# MCU_STM32H743VIT6.net
KiCad netlist of a schematic drawn in Altium Designer
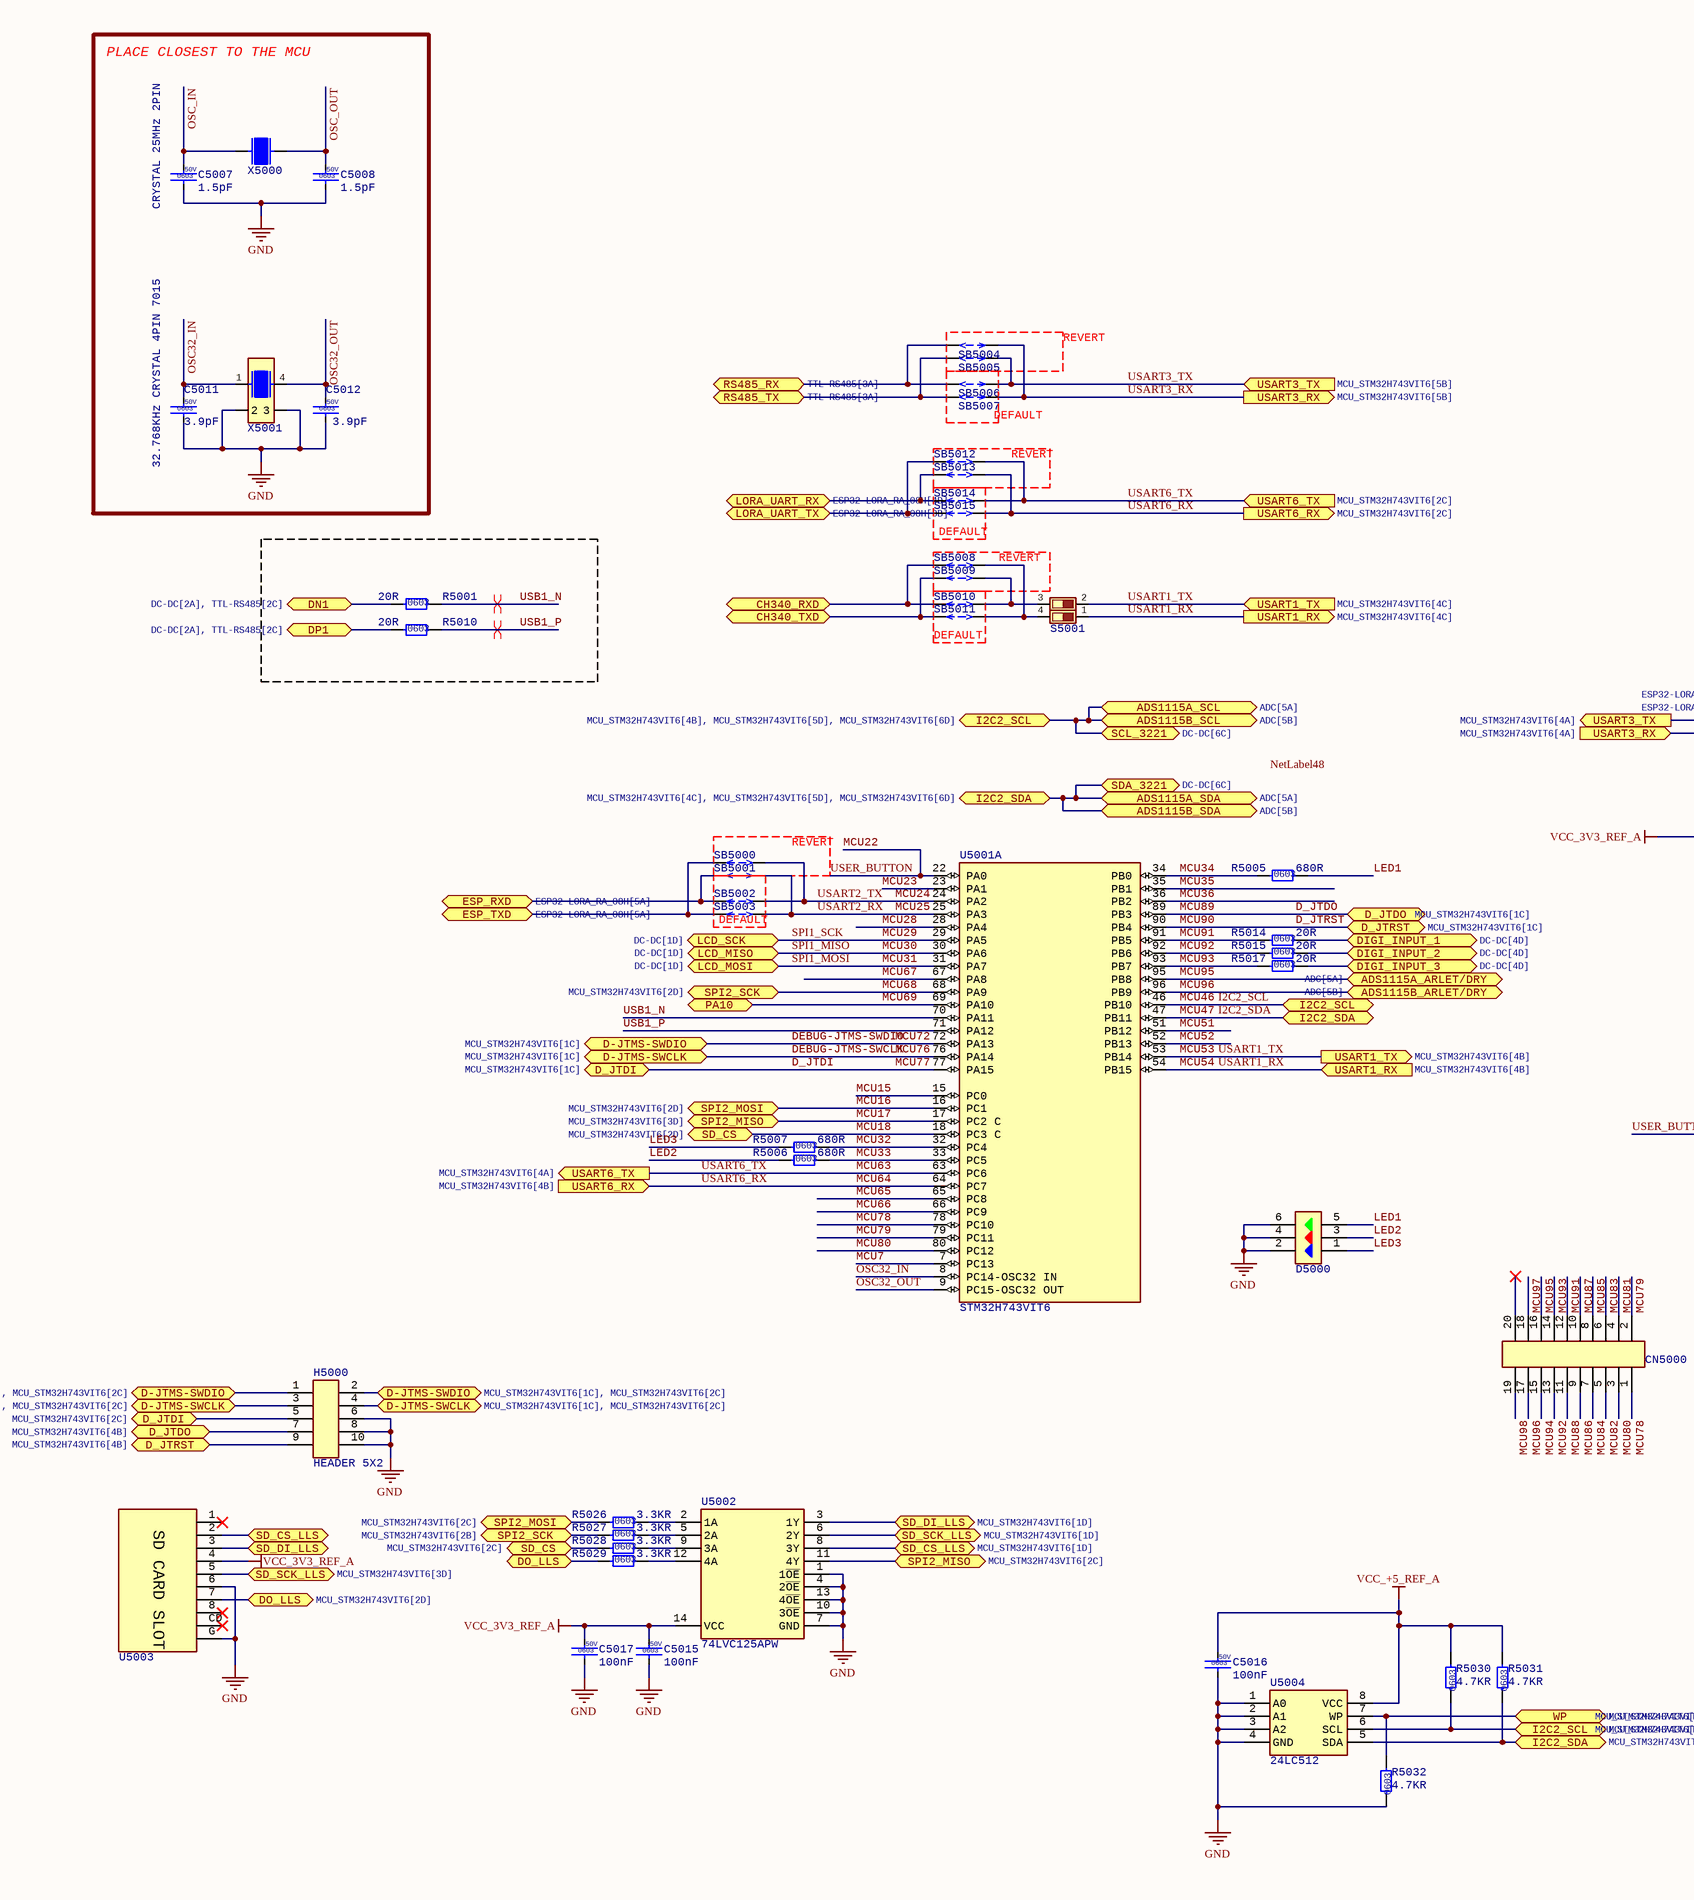
[diagram p0: MCU_STM32H743VIT6.SchDoc, left]
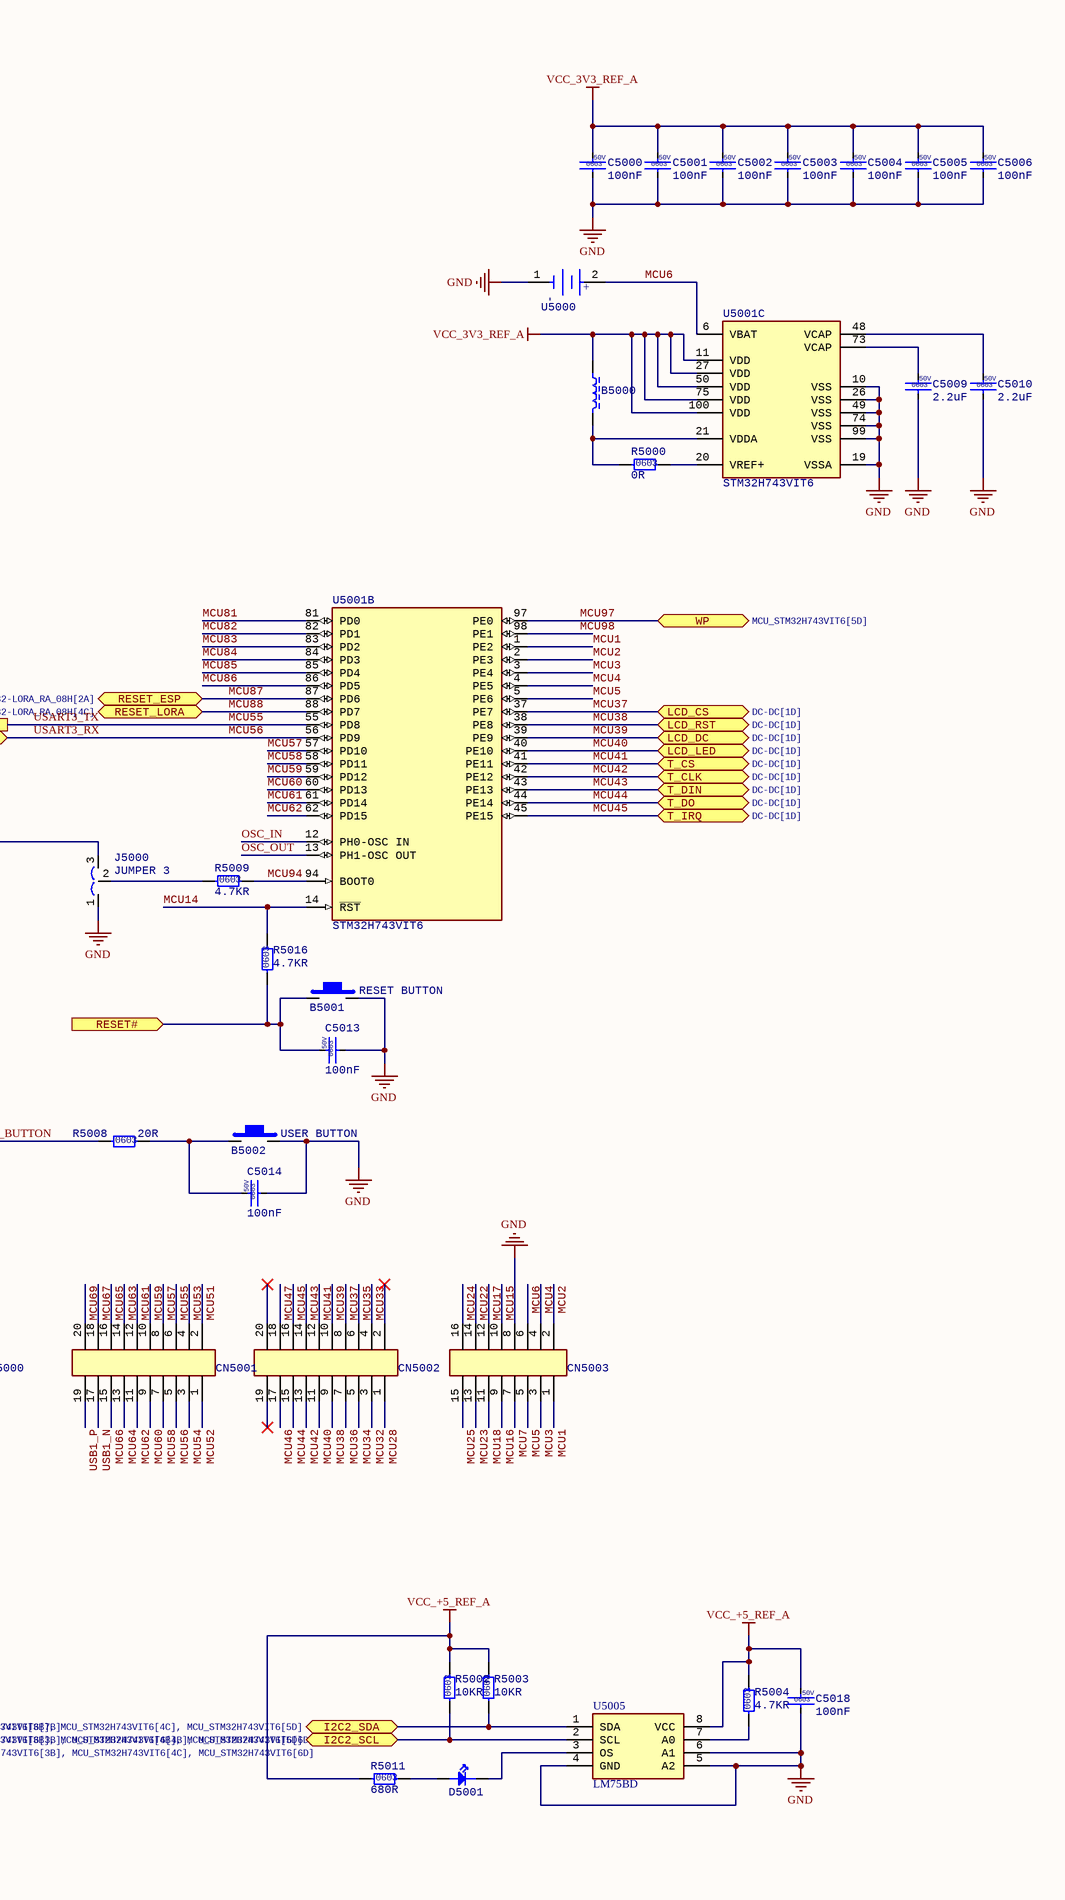
[diagram p1: MCU_STM32H743VIT6.SchDoc, right]

(export (version "E")
  (design (tool "Eeschema 10.0.6"))
  (components
    (comp (ref "B5000")
      (value "FERRITE BEAD 600 OHM")
      (footprint "FERRITE BEAD 0603")
      (description "FERRITE BEAD 600 OHM 0603 1LN")
      (libsource (lib "FF_FINAL_PROJECT") (part "FERRITE BEAD"))
    )
    (comp (ref "B5001")
      (value "RESET BUTTON")
      (footprint "TACTILE 3X4MM")
      (description "Nút Nhấn 3x4mm Cao 2.5mm 2 Chân SMD")
      (libsource (lib "FF_FINAL_PROJECT") (part "TACTILE 3X4MM"))
    )
    (comp (ref "B5002")
      (value "USER BUTTON")
      (footprint "TACTILE 3X4MM")
      (description "Nút Nhấn 3x4mm Cao 2.5mm 2 Chân SMD")
      (libsource (lib "FF_FINAL_PROJECT") (part "TACTILE 3X4MM"))
    )
    (comp (ref "C5000")
      (value "100nF")
      (footprint "CAP CER 0603")
      (description "CAP CER SMD 100nF 10% 50V 0603")
      (fields (field (name "VOLTAGE") "50V") (field (name "SIZE") "0603") (field (name "TOLERANCE") "10%"))
      (libsource (lib "FF_FINAL_PROJECT") (part "CAPACITOR CERAMIC"))
    )
    (comp (ref "C5001")
      (value "100nF")
      (footprint "CAP CER 0603")
      (description "CAP CER SMD 100nF 10% 50V 0603")
      (fields (field (name "VOLTAGE") "50V") (field (name "SIZE") "0603") (field (name "TOLERANCE") "10%"))
      (libsource (lib "FF_FINAL_PROJECT") (part "CAPACITOR CERAMIC"))
    )
    (comp (ref "C5002")
      (value "100nF")
      (footprint "CAP CER 0603")
      (description "CAP CER SMD 100nF 10% 50V 0603")
      (fields (field (name "VOLTAGE") "50V") (field (name "SIZE") "0603") (field (name "TOLERANCE") "10%"))
      (libsource (lib "FF_FINAL_PROJECT") (part "CAPACITOR CERAMIC"))
    )
    (comp (ref "C5003")
      (value "100nF")
      (footprint "CAP CER 0603")
      (description "CAP CER SMD 100nF 10% 50V 0603")
      (fields (field (name "VOLTAGE") "50V") (field (name "SIZE") "0603") (field (name "TOLERANCE") "10%"))
      (libsource (lib "FF_FINAL_PROJECT") (part "CAPACITOR CERAMIC"))
    )
    (comp (ref "C5004")
      (value "100nF")
      (footprint "CAP CER 0603")
      (description "CAP CER SMD 100nF 10% 50V 0603")
      (fields (field (name "VOLTAGE") "50V") (field (name "SIZE") "0603") (field (name "TOLERANCE") "10%"))
      (libsource (lib "FF_FINAL_PROJECT") (part "CAPACITOR CERAMIC"))
    )
    (comp (ref "C5005")
      (value "100nF")
      (footprint "CAP CER 0603")
      (description "CAP CER SMD 100nF 10% 50V 0603")
      (fields (field (name "VOLTAGE") "50V") (field (name "SIZE") "0603") (field (name "TOLERANCE") "10%"))
      (libsource (lib "FF_FINAL_PROJECT") (part "CAPACITOR CERAMIC"))
    )
    (comp (ref "C5006")
      (value "100nF")
      (footprint "CAP CER 0603")
      (description "CAP CER SMD 100nF 10% 50V 0603")
      (fields (field (name "VOLTAGE") "50V") (field (name "SIZE") "0603") (field (name "TOLERANCE") "10%"))
      (libsource (lib "FF_FINAL_PROJECT") (part "CAPACITOR CERAMIC"))
    )
    (comp (ref "C5007")
      (value "1.5pF")
      (footprint "CAP CER 0603")
      (description "CAP CER SMD 1.5pF 10% 50V 0603")
      (fields (field (name "VOLTAGE") "50V") (field (name "SIZE") "0603") (field (name "TOLERANCE") "10%"))
      (libsource (lib "FF_FINAL_PROJECT") (part "CAPACITOR CERAMIC"))
    )
    (comp (ref "C5008")
      (value "1.5pF")
      (footprint "CAP CER 0603")
      (description "CAP CER SMD 1.5pF 10% 50V 0603")
      (fields (field (name "VOLTAGE") "50V") (field (name "SIZE") "0603") (field (name "TOLERANCE") "10%"))
      (libsource (lib "FF_FINAL_PROJECT") (part "CAPACITOR CERAMIC"))
    )
    (comp (ref "C5009")
      (value "2.2uF")
      (footprint "CAP CER 0603")
      (description "CAP CER SMD 2.2uF 10% 50V 0603")
      (fields (field (name "VOLTAGE") "50V") (field (name "SIZE") "0603") (field (name "TOLERANCE") "10%"))
      (libsource (lib "FF_FINAL_PROJECT") (part "CAPACITOR CERAMIC"))
    )
    (comp (ref "C5010")
      (value "2.2uF")
      (footprint "CAP CER 0603")
      (description "CAP CER SMD 2.2uF 10% 50V 0603")
      (fields (field (name "VOLTAGE") "50V") (field (name "SIZE") "0603") (field (name "TOLERANCE") "10%"))
      (libsource (lib "FF_FINAL_PROJECT") (part "CAPACITOR CERAMIC"))
    )
    (comp (ref "C5011")
      (value "3.9pF")
      (footprint "CAP CER 0603")
      (description "CAP CER SMD 3.9pF 10% 50V 0603")
      (fields (field (name "VOLTAGE") "50V") (field (name "SIZE") "0603") (field (name "TOLERANCE") "10%"))
      (libsource (lib "FF_FINAL_PROJECT") (part "CAPACITOR CERAMIC"))
    )
    (comp (ref "C5012")
      (value "3.9pF")
      (footprint "CAP CER 0603")
      (description "CAP CER SMD 3.9pF 10% 50V 0603")
      (fields (field (name "VOLTAGE") "50V") (field (name "SIZE") "0603") (field (name "TOLERANCE") "10%"))
      (libsource (lib "FF_FINAL_PROJECT") (part "CAPACITOR CERAMIC"))
    )
    (comp (ref "C5013")
      (value "100nF")
      (footprint "CAP CER 0603")
      (description "CAP CER SMD 100nF 10% 50V 0603")
      (fields (field (name "VOLTAGE") "50V") (field (name "SIZE") "0603") (field (name "TOLERANCE") "10%"))
      (libsource (lib "FF_FINAL_PROJECT") (part "CAPACITOR CERAMIC"))
    )
    (comp (ref "C5014")
      (value "100nF")
      (footprint "CAP CER 0603")
      (description "CAP CER SMD 100nF 10% 50V 0603")
      (fields (field (name "VOLTAGE") "50V") (field (name "SIZE") "0603") (field (name "TOLERANCE") "10%"))
      (libsource (lib "FF_FINAL_PROJECT") (part "CAPACITOR CERAMIC"))
    )
    (comp (ref "C5015")
      (value "100nF")
      (footprint "CAP CER 0603")
      (description "CAP CER SMD 100nF 10% 50V 0603")
      (fields (field (name "VOLTAGE") "50V") (field (name "SIZE") "0603") (field (name "TOLERANCE") "10%"))
      (libsource (lib "FF_FINAL_PROJECT") (part "CAPACITOR CERAMIC"))
    )
    (comp (ref "C5016")
      (value "100nF")
      (footprint "CAP CER 0603")
      (description "CAP CER SMD 100nF 10% 50V 0603")
      (fields (field (name "VOLTAGE") "50V") (field (name "SIZE") "0603") (field (name "TOLERANCE") "10%"))
      (libsource (lib "FF_FINAL_PROJECT") (part "CAPACITOR CERAMIC"))
    )
    (comp (ref "C5017")
      (value "100nF")
      (footprint "CAP CER 0603")
      (description "CAP CER SMD 100nF 10% 50V 0603")
      (fields (field (name "VOLTAGE") "50V") (field (name "SIZE") "0603") (field (name "TOLERANCE") "10%"))
      (libsource (lib "FF_FINAL_PROJECT") (part "CAPACITOR CERAMIC"))
    )
    (comp (ref "C5018")
      (value "100nF")
      (footprint "CAP CER 0603")
      (description "CAP CER SMD 100nF 10% 50V 0603")
      (fields (field (name "VOLTAGE") "50V") (field (name "SIZE") "0603") (field (name "TOLERANCE") "10%"))
      (libsource (lib "FF_FINAL_PROJECT") (part "CAPACITOR CERAMIC"))
    )
    (comp (ref "CN5000")
      (value "SMD HEADER 10X2X2.54MM")
      (footprint "SMD HEADER 10X2X2.54MM")
      (libsource (lib "FF_FINAL_PROJECT") (part "SMD HEADER 10X2X2.54MM"))
    )
    (comp (ref "CN5001")
      (value "SMD HEADER 10X2X2.54MM")
      (footprint "SMD HEADER 10X2X2.54MM")
      (libsource (lib "FF_FINAL_PROJECT") (part "SMD HEADER 10X2X2.54MM"))
    )
    (comp (ref "CN5002")
      (value "SMD HEADER 10X2X2.54MM")
      (footprint "SMD HEADER 10X2X2.54MM")
      (libsource (lib "FF_FINAL_PROJECT") (part "SMD HEADER 10X2X2.54MM"))
    )
    (comp (ref "CN5003")
      (value "SMD HEADER 8X2X2.54MM")
      (footprint "SMD HEADER 8X2X2.54MM")
      (libsource (lib "FF_FINAL_PROJECT") (part "SMD HEADER 8X2X2.54MM"))
    )
    (comp (ref "D5000")
      (value "LED RGB 5050")
      (footprint "LED RGB 5050")
      (description "LED RGB 5050 Dán SMD Trong Suốt")
      (libsource (lib "FF_FINAL_PROJECT") (part "LED RGB"))
    )
    (comp (ref "D5001")
      (value "LED RED")
      (footprint "LED RED 0603")
      (description "LED RED 0603")
      (libsource (lib "FF_FINAL_PROJECT") (part "LED"))
    )
    (comp (ref "H5000")
      (value "HEADER 5X2")
      (footprint "HEADER 5X2")
      (libsource (lib "FF_FINAL_PROJECT") (part "HEADER 5X2"))
    )
    (comp (ref "J5000")
      (value "JUMPER 3")
      (footprint "JUMPER 3")
      (libsource (lib "FF_FINAL_PROJECT") (part "JUMPER 3"))
    )
    (comp (ref "R5000")
      (value "0R")
      (footprint "RESC 0603(1608) SMD")
      (description "RESISTOR SMD 0R OHM 1% 100mW 0603")
      (fields (field (name "SIZE") "0603") (field (name "TOLERANCE") "1%"))
      (libsource (lib "FF_FINAL_PROJECT") (part "RESISTOR"))
    )
    (comp (ref "R5001")
      (value "20R")
      (footprint "RESC 0603(1608) SMD")
      (description "RESISTOR SMD 20R OHM 1% 100mW 0603")
      (fields (field (name "SIZE") "0603") (field (name "TOLERANCE") "1%"))
      (libsource (lib "FF_FINAL_PROJECT") (part "RESISTOR"))
    )
    (comp (ref "R5002")
      (value "10KR")
      (footprint "RESC 0603(1608) SMD")
      (description "RESISTOR SMD 10KR OHM 1% 100mW 0603")
      (fields (field (name "SIZE") "0603") (field (name "TOLERANCE") "1%"))
      (libsource (lib "") (part "RESISTOR_2"))
    )
    (comp (ref "R5003")
      (value "10KR")
      (footprint "RESC 0603(1608) SMD")
      (description "RESISTOR SMD 10KR OHM 1% 100mW 0603")
      (fields (field (name "SIZE") "0603") (field (name "TOLERANCE") "1%"))
      (libsource (lib "") (part "RESISTOR_2"))
    )
    (comp (ref "R5004")
      (value "4.7KR")
      (footprint "RESC 0603(1608) SMD")
      (description "RESISTOR SMD 4.7KR OHM 1% 100mW 0603")
      (fields (field (name "SIZE") "0603") (field (name "TOLERANCE") "1%"))
      (libsource (lib "") (part "RESISTOR_2"))
    )
    (comp (ref "R5005")
      (value "680R")
      (footprint "RESC 0603(1608) SMD")
      (description "RESISTOR SMD 680R OHM 5% 100mW 0603")
      (fields (field (name "SIZE") "0603") (field (name "TOLERANCE") "5%"))
      (libsource (lib "FF_FINAL_PROJECT") (part "RESISTOR"))
    )
    (comp (ref "R5006")
      (value "680R")
      (footprint "RESC 0603(1608) SMD")
      (description "RESISTOR SMD 680R OHM 5% 100mW 0603")
      (fields (field (name "SIZE") "0603") (field (name "TOLERANCE") "5%"))
      (libsource (lib "FF_FINAL_PROJECT") (part "RESISTOR"))
    )
    (comp (ref "R5007")
      (value "680R")
      (footprint "RESC 0603(1608) SMD")
      (description "RESISTOR SMD 680R OHM 5% 100mW 0603")
      (fields (field (name "SIZE") "0603") (field (name "TOLERANCE") "5%"))
      (libsource (lib "FF_FINAL_PROJECT") (part "RESISTOR"))
    )
    (comp (ref "R5008")
      (value "20R")
      (footprint "RESC 0603(1608) SMD")
      (description "RESISTOR SMD 20R OHM 1% 100mW 0603")
      (fields (field (name "SIZE") "0603") (field (name "TOLERANCE") "1%"))
      (libsource (lib "FF_FINAL_PROJECT") (part "RESISTOR"))
    )
    (comp (ref "R5009")
      (value "4.7KR")
      (footprint "RESC 0603(1608) SMD")
      (description "RESISTOR SMD 4.7KR OHM 1% 100mW 0603")
      (fields (field (name "SIZE") "0603") (field (name "TOLERANCE") "1%"))
      (libsource (lib "FF_FINAL_PROJECT") (part "RESISTOR"))
    )
    (comp (ref "R5010")
      (value "20R")
      (footprint "RESC 0603(1608) SMD")
      (description "RESISTOR SMD 20R OHM 1% 100mW 0603")
      (fields (field (name "SIZE") "0603") (field (name "TOLERANCE") "1%"))
      (libsource (lib "FF_FINAL_PROJECT") (part "RESISTOR"))
    )
    (comp (ref "R5011")
      (value "680R")
      (footprint "RESC 0603(1608) SMD")
      (description "RESISTOR SMD 680R OHM 5% 100mW 0603")
      (fields (field (name "SIZE") "0603") (field (name "TOLERANCE") "5%"))
      (libsource (lib "FF_FINAL_PROJECT") (part "RESISTOR"))
    )
    (comp (ref "R5014")
      (value "20R")
      (footprint "RESC 0603(1608) SMD")
      (description "RESISTOR SMD 20R OHM 1% 100mW 0603")
      (fields (field (name "SIZE") "0603") (field (name "TOLERANCE") "1%"))
      (libsource (lib "FF_FINAL_PROJECT") (part "RESISTOR"))
    )
    (comp (ref "R5015")
      (value "20R")
      (footprint "RESC 0603(1608) SMD")
      (description "RESISTOR SMD 20R OHM 1% 100mW 0603")
      (fields (field (name "SIZE") "0603") (field (name "TOLERANCE") "1%"))
      (libsource (lib "FF_FINAL_PROJECT") (part "RESISTOR"))
    )
    (comp (ref "R5016")
      (value "4.7KR")
      (footprint "RESC 0603(1608) SMD")
      (description "RESISTOR SMD 4.7KR OHM 1% 100mW 0603")
      (fields (field (name "SIZE") "0603") (field (name "TOLERANCE") "1%"))
      (libsource (lib "") (part "RESISTOR_2"))
    )
    (comp (ref "R5017")
      (value "20R")
      (footprint "RESC 0603(1608) SMD")
      (description "RESISTOR SMD 20R OHM 1% 100mW 0603")
      (fields (field (name "SIZE") "0603") (field (name "TOLERANCE") "1%"))
      (libsource (lib "FF_FINAL_PROJECT") (part "RESISTOR"))
    )
    (comp (ref "R5026")
      (value "3.3KR")
      (footprint "RESC 0603(1608) SMD")
      (description "RESISTOR SMD 3.3KR OHM 1% 100mW 0603")
      (fields (field (name "SIZE") "0603") (field (name "TOLERANCE") "1%"))
      (libsource (lib "FF_FINAL_PROJECT") (part "RESISTOR"))
    )
    (comp (ref "R5027")
      (value "3.3KR")
      (footprint "RESC 0603(1608) SMD")
      (description "RESISTOR SMD 3.3KR OHM 1% 100mW 0603")
      (fields (field (name "SIZE") "0603") (field (name "TOLERANCE") "1%"))
      (libsource (lib "FF_FINAL_PROJECT") (part "RESISTOR"))
    )
    (comp (ref "R5028")
      (value "3.3KR")
      (footprint "RESC 0603(1608) SMD")
      (description "RESISTOR SMD 3.3KR OHM 1% 100mW 0603")
      (fields (field (name "SIZE") "0603") (field (name "TOLERANCE") "1%"))
      (libsource (lib "FF_FINAL_PROJECT") (part "RESISTOR"))
    )
    (comp (ref "R5029")
      (value "3.3KR")
      (footprint "RESC 0603(1608) SMD")
      (description "RESISTOR SMD 3.3KR OHM 1% 100mW 0603")
      (fields (field (name "SIZE") "0603") (field (name "TOLERANCE") "1%"))
      (libsource (lib "FF_FINAL_PROJECT") (part "RESISTOR"))
    )
    (comp (ref "R5030")
      (value "4.7KR")
      (footprint "RESC 0603(1608) SMD")
      (description "RESISTOR SMD 4.7KR OHM 1% 100mW 0603")
      (fields (field (name "SIZE") "0603") (field (name "TOLERANCE") "1%"))
      (libsource (lib "") (part "RESISTOR_1"))
    )
    (comp (ref "R5031")
      (value "4.7KR")
      (footprint "RESC 0603(1608) SMD")
      (description "RESISTOR SMD 4.7KR OHM 1% 100mW 0603")
      (fields (field (name "SIZE") "0603") (field (name "TOLERANCE") "1%"))
      (libsource (lib "") (part "RESISTOR_1"))
    )
    (comp (ref "R5032")
      (value "4.7KR")
      (footprint "RESC 0603(1608) SMD")
      (description "RESISTOR SMD 4.7KR OHM 1% 100mW 0603")
      (fields (field (name "SIZE") "0603") (field (name "TOLERANCE") "1%"))
      (libsource (lib "") (part "RESISTOR_1"))
    )
    (comp (ref "S5001")
      (value "DIP-2")
      (footprint "DIP-2 SWITCH")
      (description "DIP SWITCH 1.27mm 2 CONTACT")
      (libsource (lib "FF_FINAL_PROJECT") (part "DIP-2 SWITCH"))
    )
    (comp (ref "SB5000")
      (value "SB")
      (footprint "SB")
      (description "RESISTOR SMD 0R OHM 1% 100mW 0603")
      (fields (field (name "TOLERANCE") "1%"))
      (libsource (lib "FF_FINAL_PROJECT") (part "SB"))
    )
    (comp (ref "SB5001")
      (value "SB")
      (footprint "SB")
      (description "RESISTOR SMD 0R OHM 1% 100mW 0603")
      (fields (field (name "TOLERANCE") "1%"))
      (libsource (lib "FF_FINAL_PROJECT") (part "SB"))
    )
    (comp (ref "SB5002")
      (value "SB")
      (footprint "SB")
      (description "RESISTOR SMD 0R OHM 1% 100mW 0603")
      (fields (field (name "TOLERANCE") "1%"))
      (libsource (lib "FF_FINAL_PROJECT") (part "SB"))
    )
    (comp (ref "SB5003")
      (value "SB")
      (footprint "SB")
      (description "RESISTOR SMD 0R OHM 1% 100mW 0603")
      (fields (field (name "TOLERANCE") "1%"))
      (libsource (lib "FF_FINAL_PROJECT") (part "SB"))
    )
    (comp (ref "SB5004")
      (value "SB")
      (footprint "SB")
      (description "RESISTOR SMD 0R OHM 1% 100mW 0603")
      (fields (field (name "TOLERANCE") "1%"))
      (libsource (lib "FF_FINAL_PROJECT") (part "SB"))
    )
    (comp (ref "SB5005")
      (value "SB")
      (footprint "SB")
      (description "RESISTOR SMD 0R OHM 1% 100mW 0603")
      (fields (field (name "TOLERANCE") "1%"))
      (libsource (lib "FF_FINAL_PROJECT") (part "SB"))
    )
    (comp (ref "SB5006")
      (value "SB")
      (footprint "SB")
      (description "RESISTOR SMD 0R OHM 1% 100mW 0603")
      (fields (field (name "TOLERANCE") "1%"))
      (libsource (lib "FF_FINAL_PROJECT") (part "SB"))
    )
    (comp (ref "SB5007")
      (value "SB")
      (footprint "SB")
      (description "RESISTOR SMD 0R OHM 1% 100mW 0603")
      (fields (field (name "TOLERANCE") "1%"))
      (libsource (lib "FF_FINAL_PROJECT") (part "SB"))
    )
    (comp (ref "SB5008")
      (value "SB")
      (footprint "SB")
      (description "RESISTOR SMD 0R OHM 1% 100mW 0603")
      (fields (field (name "TOLERANCE") "1%"))
      (libsource (lib "FF_FINAL_PROJECT") (part "SB"))
    )
    (comp (ref "SB5009")
      (value "SB")
      (footprint "SB")
      (description "RESISTOR SMD 0R OHM 1% 100mW 0603")
      (fields (field (name "TOLERANCE") "1%"))
      (libsource (lib "FF_FINAL_PROJECT") (part "SB"))
    )
    (comp (ref "SB5010")
      (value "SB")
      (footprint "SB")
      (description "RESISTOR SMD 0R OHM 1% 100mW 0603")
      (fields (field (name "TOLERANCE") "1%"))
      (libsource (lib "FF_FINAL_PROJECT") (part "SB"))
    )
    (comp (ref "SB5011")
      (value "SB")
      (footprint "SB")
      (description "RESISTOR SMD 0R OHM 1% 100mW 0603")
      (fields (field (name "TOLERANCE") "1%"))
      (libsource (lib "FF_FINAL_PROJECT") (part "SB"))
    )
    (comp (ref "SB5012")
      (value "SB")
      (footprint "SB")
      (description "RESISTOR SMD 0R OHM 1% 100mW 0603")
      (fields (field (name "TOLERANCE") "1%"))
      (libsource (lib "FF_FINAL_PROJECT") (part "SB"))
    )
    (comp (ref "SB5013")
      (value "SB")
      (footprint "SB")
      (description "RESISTOR SMD 0R OHM 1% 100mW 0603")
      (fields (field (name "TOLERANCE") "1%"))
      (libsource (lib "FF_FINAL_PROJECT") (part "SB"))
    )
    (comp (ref "SB5014")
      (value "SB")
      (footprint "SB")
      (description "RESISTOR SMD 0R OHM 1% 100mW 0603")
      (fields (field (name "TOLERANCE") "1%"))
      (libsource (lib "FF_FINAL_PROJECT") (part "SB"))
    )
    (comp (ref "SB5015")
      (value "SB")
      (footprint "SB")
      (description "RESISTOR SMD 0R OHM 1% 100mW 0603")
      (fields (field (name "TOLERANCE") "1%"))
      (libsource (lib "FF_FINAL_PROJECT") (part "SB"))
    )
    (comp (ref "U5000")
      (value "BS-6")
      (footprint "BS-6")
      (description "BS-6 Đế Pin CR2032 CR2025 Dán SMD")
      (libsource (lib "FF_FINAL_PROJECT") (part "BS-6"))
    )
    (comp (ref "U5001")
      (value "STM32H743VIT6")
      (footprint "LQFP-100-A")
      (description "32-bit Arm® Cortex®-M7 480MHz MCUs, up to 2MB flash, up to 1MB RAM, 46 com. and analog interfaces")
      (libsource (lib "FF_FINAL_PROJECT") (part "STM32H743VIT6"))
    )
    (comp (ref "U5002")
      (value "74LVC125APW")
      (footprint "TSSOP-14")
      (description "Quad buffer/line driver with 5 V tolerant input/outputs; 3-state")
      (libsource (lib "FF_FINAL_PROJECT") (part "74LVC125APW"))
    )
    (comp (ref "U5003")
      (value "MiSD-PP-9P-V2")
      (footprint "MiSD-PP-9P-V2")
      (description "SDCARD SLOT 9 PIN PUSH PULL")
      (libsource (lib "FF_FINAL_PROJECT") (part "MiSD-PP-9P-V2"))
    )
    (comp (ref "U5004")
      (value "24LC512")
      (footprint "SOIC-8")
      (description "512K I2C Serial EEPROM")
      (libsource (lib "FF_FINAL_PROJECT") (part "24LC512"))
    )
    (comp (ref "U5005")
      (value "LM75BD")
      (footprint "SOP-8")
      (description "Digital temperature sensor and thermal watchdog")
      (libsource (lib "FF_FINAL_PROJECT") (part "LM75BD"))
    )
    (comp (ref "X5000")
      (value "CRYSTAL 25MHz 2PIN")
      (footprint "CRYSTAL 5032 2PIN")
      (description "CRYSTAL 25MHz 2PIN SMD 5 x 3.2mm, ±20ppm 12pF")
      (libsource (lib "FF_FINAL_PROJECT") (part "CRYSTAL 2PIN"))
    )
    (comp (ref "X5001")
      (value "32.768KHz CRYSTAL 4PIN 7015")
      (footprint "CRYSTAL 32.768KHz 7015")
      (description "32.768kHz ±20ppm, 9pF 65kOhm, 7x1.5x1.4 mm")
      (libsource (lib "FF_FINAL_PROJECT") (part "CRYSTAL 4PIN"))
    )
  )
  (nets
    (net (code "1") (name "/CH340_RXD") (class "Default")
      (node (ref "SB5008") (pin "1") (pinfunction "1_1") (pintype "passive"))
      (node (ref "SB5010") (pin "1") (pinfunction "1_1") (pintype "passive"))
    )
    (net (code "2") (name "/CH340_TXD") (class "Default")
      (node (ref "SB5009") (pin "1") (pinfunction "1_1") (pintype "passive"))
      (node (ref "SB5011") (pin "1") (pinfunction "1_1") (pintype "passive"))
    )
    (net (code "3") (name "/DEBUG-JTMS-SWCLK") (class "Default")
      (node (ref "H5000") (pin "3") (pinfunction "3_3") (pintype "passive"))
      (node (ref "H5000") (pin "4") (pinfunction "4_4") (pintype "passive"))
      (node (ref "U5001") (pin "76") (pinfunction "PA14_76") (pintype "bidirectional"))
    )
    (net (code "4") (name "/DEBUG-JTMS-SWDIO") (class "Default")
      (node (ref "H5000") (pin "1") (pinfunction "1_1") (pintype "passive"))
      (node (ref "H5000") (pin "2") (pinfunction "2_2") (pintype "passive"))
      (node (ref "U5001") (pin "72") (pinfunction "PA13_72") (pintype "bidirectional"))
    )
    (net (code "5") (name "/DIGI_INPUT_1") (class "Default")
      (node (ref "R5014") (pin "2") (pinfunction "2_2") (pintype "passive"))
    )
    (net (code "6") (name "/DIGI_INPUT_2") (class "Default")
      (node (ref "R5015") (pin "2") (pinfunction "2_2") (pintype "passive"))
    )
    (net (code "7") (name "/DIGI_INPUT_3") (class "Default")
      (node (ref "R5017") (pin "2") (pinfunction "2_2") (pintype "passive"))
    )
    (net (code "8") (name "/DN1") (class "Default")
      (node (ref "R5001") (pin "1") (pinfunction "1_1") (pintype "passive"))
    )
    (net (code "9") (name "/DO_LLS") (class "Default")
      (node (ref "R5029") (pin "1") (pinfunction "1_1") (pintype "passive"))
      (node (ref "U5003") (pin "7") (pinfunction "7_7") (pintype "passive"))
    )
    (net (code "10") (name "/DP1") (class "Default")
      (node (ref "R5010") (pin "1") (pinfunction "1_1") (pintype "passive"))
    )
    (net (code "11") (name "/D_JTDI") (class "Default")
      (node (ref "H5000") (pin "5") (pinfunction "5_5") (pintype "passive"))
      (node (ref "U5001") (pin "77") (pinfunction "PA15_77") (pintype "bidirectional"))
    )
    (net (code "12") (name "/D_JTDO") (class "Default")
      (node (ref "H5000") (pin "7") (pinfunction "7_7") (pintype "passive"))
      (node (ref "U5001") (pin "89") (pinfunction "PB3_89") (pintype "bidirectional"))
    )
    (net (code "13") (name "/D_JTRST") (class "Default")
      (node (ref "H5000") (pin "9") (pinfunction "9_9") (pintype "passive"))
      (node (ref "U5001") (pin "90") (pinfunction "PB4_90") (pintype "bidirectional"))
    )
    (net (code "14") (name "/ESP_RXD") (class "Default")
      (node (ref "SB5001") (pin "1") (pinfunction "1_1") (pintype "passive"))
      (node (ref "SB5002") (pin "1") (pinfunction "1_1") (pintype "passive"))
    )
    (net (code "15") (name "/ESP_TXD") (class "Default")
      (node (ref "SB5000") (pin "1") (pinfunction "1_1") (pintype "passive"))
      (node (ref "SB5003") (pin "1") (pinfunction "1_1") (pintype "passive"))
    )
    (net (code "16") (name "/I2C2_SCL") (class "Default")
      (node (ref "CN5002") (pin "17") (pinfunction "17_17") (pintype "passive"))
      (node (ref "R5002") (pin "1") (pinfunction "1_1") (pintype "passive"))
      (node (ref "R5030") (pin "2") (pinfunction "2_2") (pintype "passive"))
      (node (ref "U5001") (pin "46") (pinfunction "PB10_46") (pintype "bidirectional"))
      (node (ref "U5004") (pin "6") (pinfunction "SCL_6") (pintype "passive"))
      (node (ref "U5005") (pin "2") (pinfunction "SCL_2") (pintype "passive"))
    )
    (net (code "17") (name "/I2C2_SDA") (class "Default")
      (node (ref "CN5002") (pin "18") (pinfunction "18_18") (pintype "passive"))
      (node (ref "R5003") (pin "1") (pinfunction "1_1") (pintype "passive"))
      (node (ref "R5031") (pin "2") (pinfunction "2_2") (pintype "passive"))
      (node (ref "U5001") (pin "47") (pinfunction "PB11_47") (pintype "bidirectional"))
      (node (ref "U5004") (pin "5") (pinfunction "SDA_5") (pintype "passive"))
      (node (ref "U5005") (pin "1") (pinfunction "SDA_1") (pintype "passive"))
    )
    (net (code "18") (name "/LED1") (class "Default")
      (node (ref "D5000") (pin "5") (pinfunction "5_5") (pintype "passive"))
      (node (ref "R5005") (pin "2") (pinfunction "2_2") (pintype "passive"))
    )
    (net (code "19") (name "/LED2") (class "Default")
      (node (ref "D5000") (pin "3") (pinfunction "3_3") (pintype "passive"))
      (node (ref "R5006") (pin "1") (pinfunction "1_1") (pintype "passive"))
    )
    (net (code "20") (name "/LED3") (class "Default")
      (node (ref "D5000") (pin "1") (pinfunction "1_1") (pintype "passive"))
      (node (ref "R5007") (pin "1") (pinfunction "1_1") (pintype "passive"))
    )
    (net (code "21") (name "/LORA_UART_RX") (class "Default")
      (node (ref "SB5013") (pin "1") (pinfunction "1_1") (pintype "passive"))
      (node (ref "SB5014") (pin "1") (pinfunction "1_1") (pintype "passive"))
    )
    (net (code "22") (name "/LORA_UART_TX") (class "Default")
      (node (ref "SB5012") (pin "1") (pinfunction "1_1") (pintype "passive"))
      (node (ref "SB5015") (pin "1") (pinfunction "1_1") (pintype "passive"))
    )
    (net (code "23") (name "/MCU1") (class "Default")
      (node (ref "CN5003") (pin "1") (pinfunction "1_1") (pintype "passive"))
      (node (ref "U5001") (pin "1") (pinfunction "PE2_1") (pintype "bidirectional"))
    )
    (net (code "24") (name "/MCU2") (class "Default")
      (node (ref "CN5003") (pin "2") (pinfunction "2_2") (pintype "passive"))
      (node (ref "U5001") (pin "2") (pinfunction "PE3_2") (pintype "bidirectional"))
    )
    (net (code "25") (name "/MCU3") (class "Default")
      (node (ref "CN5003") (pin "3") (pinfunction "3_3") (pintype "passive"))
      (node (ref "U5001") (pin "3") (pinfunction "PE4_3") (pintype "bidirectional"))
    )
    (net (code "26") (name "/MCU4") (class "Default")
      (node (ref "CN5003") (pin "4") (pinfunction "4_4") (pintype "passive"))
      (node (ref "U5001") (pin "4") (pinfunction "PE5_4") (pintype "bidirectional"))
    )
    (net (code "27") (name "/MCU5") (class "Default")
      (node (ref "CN5003") (pin "5") (pinfunction "5_5") (pintype "passive"))
      (node (ref "U5001") (pin "5") (pinfunction "PE6_5") (pintype "bidirectional"))
    )
    (net (code "28") (name "/MCU6") (class "Default")
      (node (ref "CN5003") (pin "6") (pinfunction "6_6") (pintype "passive"))
      (node (ref "U5000") (pin "2") (pinfunction "A_2") (pintype "passive"))
      (node (ref "U5001") (pin "6") (pinfunction "VBAT_6") (pintype "power_in"))
    )
    (net (code "29") (name "/MCU7") (class "Default")
      (node (ref "CN5003") (pin "7") (pinfunction "7_7") (pintype "passive"))
      (node (ref "U5001") (pin "7") (pinfunction "PC13_7") (pintype "bidirectional"))
    )
    (net (code "30") (name "/MCU14") (class "Default")
      (node (ref "R5016") (pin "2") (pinfunction "2_2") (pintype "passive"))
      (node (ref "U5001") (pin "14") (pinfunction "~{RST}_14") (pintype "input"))
    )
    (net (code "31") (name "/MCU15") (class "Default")
      (node (ref "CN5003") (pin "10") (pinfunction "10_10") (pintype "passive"))
      (node (ref "U5001") (pin "15") (pinfunction "PC0_15") (pintype "bidirectional"))
    )
    (net (code "32") (name "/MCU16") (class "Default")
      (node (ref "CN5003") (pin "9") (pinfunction "9_9") (pintype "passive"))
      (node (ref "R5026") (pin "1") (pinfunction "1_1") (pintype "passive"))
      (node (ref "U5001") (pin "16") (pinfunction "PC1_16") (pintype "bidirectional"))
    )
    (net (code "33") (name "/MCU17") (class "Default")
      (node (ref "CN5003") (pin "12") (pinfunction "12_12") (pintype "passive"))
      (node (ref "U5001") (pin "17") (pinfunction "PC2_C_17") (pintype "bidirectional"))
      (node (ref "U5002") (pin "11") (pinfunction "4Y_11") (pintype "passive"))
    )
    (net (code "34") (name "/MCU18") (class "Default")
      (node (ref "CN5003") (pin "11") (pinfunction "11_11") (pintype "passive"))
      (node (ref "R5028") (pin "1") (pinfunction "1_1") (pintype "passive"))
      (node (ref "U5001") (pin "18") (pinfunction "PC3_C_18") (pintype "bidirectional"))
    )
    (net (code "35") (name "/MCU22") (class "Default")
      (node (ref "CN5003") (pin "14") (pinfunction "14_14") (pintype "passive"))
      (node (ref "R5008") (pin "1") (pinfunction "1_1") (pintype "passive"))
      (node (ref "U5001") (pin "22") (pinfunction "PA0_22") (pintype "bidirectional"))
    )
    (net (code "36") (name "/MCU23") (class "Default")
      (node (ref "CN5003") (pin "13") (pinfunction "13_13") (pintype "passive"))
      (node (ref "U5001") (pin "23") (pinfunction "PA1_23") (pintype "bidirectional"))
    )
    (net (code "37") (name "/MCU24") (class "Default")
      (node (ref "CN5003") (pin "16") (pinfunction "16_16") (pintype "passive"))
      (node (ref "SB5000") (pin "2") (pinfunction "2_2") (pintype "passive"))
      (node (ref "SB5002") (pin "2") (pinfunction "2_2") (pintype "passive"))
      (node (ref "U5001") (pin "24") (pinfunction "PA2_24") (pintype "bidirectional"))
    )
    (net (code "38") (name "/MCU25") (class "Default")
      (node (ref "CN5003") (pin "15") (pinfunction "15_15") (pintype "passive"))
      (node (ref "SB5001") (pin "2") (pinfunction "2_2") (pintype "passive"))
      (node (ref "SB5003") (pin "2") (pinfunction "2_2") (pintype "passive"))
      (node (ref "U5001") (pin "25") (pinfunction "PA3_25") (pintype "bidirectional"))
    )
    (net (code "39") (name "/MCU28") (class "Default")
      (node (ref "CN5002") (pin "1") (pinfunction "1_1") (pintype "passive"))
      (node (ref "U5001") (pin "28") (pinfunction "PA4_28") (pintype "bidirectional"))
    )
    (net (code "40") (name "/MCU29") (class "Default")
      (node (ref "U5001") (pin "29") (pinfunction "PA5_29") (pintype "bidirectional"))
    )
    (net (code "41") (name "/MCU30") (class "Default")
      (node (ref "U5001") (pin "30") (pinfunction "PA6_30") (pintype "bidirectional"))
    )
    (net (code "42") (name "/MCU31") (class "Default")
      (node (ref "U5001") (pin "31") (pinfunction "PA7_31") (pintype "bidirectional"))
    )
    (net (code "43") (name "/MCU32") (class "Default")
      (node (ref "CN5002") (pin "3") (pinfunction "3_3") (pintype "passive"))
      (node (ref "R5007") (pin "2") (pinfunction "2_2") (pintype "passive"))
      (node (ref "U5001") (pin "32") (pinfunction "PC4_32") (pintype "bidirectional"))
    )
    (net (code "44") (name "/MCU33") (class "Default")
      (node (ref "CN5002") (pin "4") (pinfunction "4_4") (pintype "passive"))
      (node (ref "R5006") (pin "2") (pinfunction "2_2") (pintype "passive"))
      (node (ref "U5001") (pin "33") (pinfunction "PC5_33") (pintype "bidirectional"))
    )
    (net (code "45") (name "/MCU34") (class "Default")
      (node (ref "CN5002") (pin "5") (pinfunction "5_5") (pintype "passive"))
      (node (ref "R5005") (pin "1") (pinfunction "1_1") (pintype "passive"))
      (node (ref "U5001") (pin "34") (pinfunction "PB0_34") (pintype "bidirectional"))
    )
    (net (code "46") (name "/MCU35") (class "Default")
      (node (ref "CN5002") (pin "6") (pinfunction "6_6") (pintype "passive"))
      (node (ref "U5001") (pin "35") (pinfunction "PB1_35") (pintype "bidirectional"))
    )
    (net (code "47") (name "/MCU36") (class "Default")
      (node (ref "CN5002") (pin "7") (pinfunction "7_7") (pintype "passive"))
      (node (ref "U5001") (pin "36") (pinfunction "PB2_36") (pintype "bidirectional"))
    )
    (net (code "48") (name "/MCU37") (class "Default")
      (node (ref "CN5002") (pin "8") (pinfunction "8_8") (pintype "passive"))
      (node (ref "U5001") (pin "37") (pinfunction "PE7_37") (pintype "bidirectional"))
    )
    (net (code "49") (name "/MCU38") (class "Default")
      (node (ref "CN5002") (pin "9") (pinfunction "9_9") (pintype "passive"))
      (node (ref "U5001") (pin "38") (pinfunction "PE8_38") (pintype "bidirectional"))
    )
    (net (code "50") (name "/MCU39") (class "Default")
      (node (ref "CN5002") (pin "10") (pinfunction "10_10") (pintype "passive"))
      (node (ref "U5001") (pin "39") (pinfunction "PE9_39") (pintype "bidirectional"))
    )
    (net (code "51") (name "/MCU40") (class "Default")
      (node (ref "CN5002") (pin "11") (pinfunction "11_11") (pintype "passive"))
      (node (ref "U5001") (pin "40") (pinfunction "PE10_40") (pintype "bidirectional"))
    )
    (net (code "52") (name "/MCU41") (class "Default")
      (node (ref "CN5002") (pin "12") (pinfunction "12_12") (pintype "passive"))
      (node (ref "U5001") (pin "41") (pinfunction "PE11_41") (pintype "bidirectional"))
    )
    (net (code "53") (name "/MCU42") (class "Default")
      (node (ref "CN5002") (pin "13") (pinfunction "13_13") (pintype "passive"))
      (node (ref "U5001") (pin "42") (pinfunction "PE12_42") (pintype "bidirectional"))
    )
    (net (code "54") (name "/MCU43") (class "Default")
      (node (ref "CN5002") (pin "14") (pinfunction "14_14") (pintype "passive"))
      (node (ref "U5001") (pin "43") (pinfunction "PE13_43") (pintype "bidirectional"))
    )
    (net (code "55") (name "/MCU44") (class "Default")
      (node (ref "CN5002") (pin "15") (pinfunction "15_15") (pintype "passive"))
      (node (ref "U5001") (pin "44") (pinfunction "PE14_44") (pintype "bidirectional"))
    )
    (net (code "56") (name "/MCU45") (class "Default")
      (node (ref "CN5002") (pin "16") (pinfunction "16_16") (pintype "passive"))
      (node (ref "U5001") (pin "45") (pinfunction "PE15_45") (pintype "bidirectional"))
    )
    (net (code "57") (name "/MCU51") (class "Default")
      (node (ref "CN5001") (pin "2") (pinfunction "2_2") (pintype "passive"))
      (node (ref "U5001") (pin "51") (pinfunction "PB12_51") (pintype "bidirectional"))
    )
    (net (code "58") (name "/MCU52") (class "Default")
      (node (ref "CN5001") (pin "1") (pinfunction "1_1") (pintype "passive"))
      (node (ref "U5001") (pin "52") (pinfunction "PB13_52") (pintype "bidirectional"))
    )
    (net (code "59") (name "/MCU53") (class "Default")
      (node (ref "CN5001") (pin "4") (pinfunction "4_4") (pintype "passive"))
      (node (ref "S5001") (pin "2") (pinfunction "2_2") (pintype "passive"))
      (node (ref "U5001") (pin "53") (pinfunction "PB14_53") (pintype "bidirectional"))
    )
    (net (code "60") (name "/MCU54") (class "Default")
      (node (ref "CN5001") (pin "3") (pinfunction "3_3") (pintype "passive"))
      (node (ref "S5001") (pin "1") (pinfunction "1_1") (pintype "passive"))
      (node (ref "U5001") (pin "54") (pinfunction "PB15_54") (pintype "bidirectional"))
    )
    (net (code "61") (name "/MCU55") (class "Default")
      (node (ref "CN5001") (pin "6") (pinfunction "6_6") (pintype "passive"))
      (node (ref "SB5005") (pin "1") (pinfunction "1_1") (pintype "passive"))
      (node (ref "SB5006") (pin "1") (pinfunction "1_1") (pintype "passive"))
      (node (ref "U5001") (pin "55") (pinfunction "PD8_55") (pintype "bidirectional"))
    )
    (net (code "62") (name "/MCU56") (class "Default")
      (node (ref "CN5001") (pin "5") (pinfunction "5_5") (pintype "passive"))
      (node (ref "SB5004") (pin "1") (pinfunction "1_1") (pintype "passive"))
      (node (ref "SB5007") (pin "1") (pinfunction "1_1") (pintype "passive"))
      (node (ref "U5001") (pin "56") (pinfunction "PD9_56") (pintype "bidirectional"))
    )
    (net (code "63") (name "/MCU57") (class "Default")
      (node (ref "CN5001") (pin "8") (pinfunction "8_8") (pintype "passive"))
      (node (ref "U5001") (pin "57") (pinfunction "PD10_57") (pintype "bidirectional"))
    )
    (net (code "64") (name "/MCU58") (class "Default")
      (node (ref "CN5001") (pin "7") (pinfunction "7_7") (pintype "passive"))
      (node (ref "U5001") (pin "58") (pinfunction "PD11_58") (pintype "bidirectional"))
    )
    (net (code "65") (name "/MCU59") (class "Default")
      (node (ref "CN5001") (pin "10") (pinfunction "10_10") (pintype "passive"))
      (node (ref "U5001") (pin "59") (pinfunction "PD12_59") (pintype "bidirectional"))
    )
    (net (code "66") (name "/MCU60") (class "Default")
      (node (ref "CN5001") (pin "9") (pinfunction "9_9") (pintype "passive"))
      (node (ref "U5001") (pin "60") (pinfunction "PD13_60") (pintype "bidirectional"))
    )
    (net (code "67") (name "/MCU61") (class "Default")
      (node (ref "CN5001") (pin "12") (pinfunction "12_12") (pintype "passive"))
      (node (ref "U5001") (pin "61") (pinfunction "PD14_61") (pintype "bidirectional"))
    )
    (net (code "68") (name "/MCU62") (class "Default")
      (node (ref "CN5001") (pin "11") (pinfunction "11_11") (pintype "passive"))
      (node (ref "U5001") (pin "62") (pinfunction "PD15_62") (pintype "bidirectional"))
    )
    (net (code "69") (name "/MCU63") (class "Default")
      (node (ref "CN5001") (pin "14") (pinfunction "14_14") (pintype "passive"))
      (node (ref "SB5012") (pin "2") (pinfunction "2_2") (pintype "passive"))
      (node (ref "SB5014") (pin "2") (pinfunction "2_2") (pintype "passive"))
      (node (ref "U5001") (pin "63") (pinfunction "PC6_63") (pintype "bidirectional"))
    )
    (net (code "70") (name "/MCU64") (class "Default")
      (node (ref "CN5001") (pin "13") (pinfunction "13_13") (pintype "passive"))
      (node (ref "SB5013") (pin "2") (pinfunction "2_2") (pintype "passive"))
      (node (ref "SB5015") (pin "2") (pinfunction "2_2") (pintype "passive"))
      (node (ref "U5001") (pin "64") (pinfunction "PC7_64") (pintype "bidirectional"))
    )
    (net (code "71") (name "/MCU65") (class "Default")
      (node (ref "CN5001") (pin "16") (pinfunction "16_16") (pintype "passive"))
      (node (ref "U5001") (pin "65") (pinfunction "PC8_65") (pintype "bidirectional"))
    )
    (net (code "72") (name "/MCU66") (class "Default")
      (node (ref "CN5001") (pin "15") (pinfunction "15_15") (pintype "passive"))
      (node (ref "U5001") (pin "66") (pinfunction "PC9_66") (pintype "bidirectional"))
    )
    (net (code "73") (name "/MCU67") (class "Default")
      (node (ref "CN5001") (pin "18") (pinfunction "18_18") (pintype "passive"))
      (node (ref "U5001") (pin "67") (pinfunction "PA8_67") (pintype "bidirectional"))
    )
    (net (code "74") (name "/MCU68") (class "Default")
      (node (ref "R5027") (pin "1") (pinfunction "1_1") (pintype "passive"))
      (node (ref "U5001") (pin "68") (pinfunction "PA9_68") (pintype "bidirectional"))
    )
    (net (code "75") (name "/MCU69") (class "Default")
      (node (ref "CN5001") (pin "20") (pinfunction "20_20") (pintype "passive"))
      (node (ref "U5001") (pin "69") (pinfunction "PA10_69") (pintype "bidirectional"))
    )
    (net (code "76") (name "/MCU78") (class "Default")
      (node (ref "CN5000") (pin "1") (pinfunction "1_1") (pintype "passive"))
      (node (ref "U5001") (pin "78") (pinfunction "PC10_78") (pintype "bidirectional"))
    )
    (net (code "77") (name "/MCU79") (class "Default")
      (node (ref "CN5000") (pin "2") (pinfunction "2_2") (pintype "passive"))
      (node (ref "U5001") (pin "79") (pinfunction "PC11_79") (pintype "bidirectional"))
    )
    (net (code "78") (name "/MCU80") (class "Default")
      (node (ref "CN5000") (pin "3") (pinfunction "3_3") (pintype "passive"))
      (node (ref "U5001") (pin "80") (pinfunction "PC12_80") (pintype "bidirectional"))
    )
    (net (code "79") (name "/MCU81") (class "Default")
      (node (ref "CN5000") (pin "4") (pinfunction "4_4") (pintype "passive"))
      (node (ref "U5001") (pin "81") (pinfunction "PD0_81") (pintype "bidirectional"))
    )
    (net (code "80") (name "/MCU82") (class "Default")
      (node (ref "CN5000") (pin "5") (pinfunction "5_5") (pintype "passive"))
      (node (ref "U5001") (pin "82") (pinfunction "PD1_82") (pintype "bidirectional"))
    )
    (net (code "81") (name "/MCU83") (class "Default")
      (node (ref "CN5000") (pin "6") (pinfunction "6_6") (pintype "passive"))
      (node (ref "U5001") (pin "83") (pinfunction "PD2_83") (pintype "bidirectional"))
    )
    (net (code "82") (name "/MCU84") (class "Default")
      (node (ref "CN5000") (pin "7") (pinfunction "7_7") (pintype "passive"))
      (node (ref "U5001") (pin "84") (pinfunction "PD3_84") (pintype "bidirectional"))
    )
    (net (code "83") (name "/MCU85") (class "Default")
      (node (ref "CN5000") (pin "8") (pinfunction "8_8") (pintype "passive"))
      (node (ref "U5001") (pin "85") (pinfunction "PD4_85") (pintype "bidirectional"))
    )
    (net (code "84") (name "/MCU86") (class "Default")
      (node (ref "CN5000") (pin "9") (pinfunction "9_9") (pintype "passive"))
      (node (ref "U5001") (pin "86") (pinfunction "PD5_86") (pintype "bidirectional"))
    )
    (net (code "85") (name "/MCU87") (class "Default")
      (node (ref "CN5000") (pin "10") (pinfunction "10_10") (pintype "passive"))
      (node (ref "U5001") (pin "87") (pinfunction "PD6_87") (pintype "bidirectional"))
    )
    (net (code "86") (name "/MCU88") (class "Default")
      (node (ref "CN5000") (pin "11") (pinfunction "11_11") (pintype "passive"))
      (node (ref "U5001") (pin "88") (pinfunction "PD7_88") (pintype "bidirectional"))
    )
    (net (code "87") (name "/MCU91") (class "Default")
      (node (ref "CN5000") (pin "12") (pinfunction "12_12") (pintype "passive"))
      (node (ref "R5014") (pin "1") (pinfunction "1_1") (pintype "passive"))
      (node (ref "U5001") (pin "91") (pinfunction "PB5_91") (pintype "bidirectional"))
    )
    (net (code "88") (name "/MCU92") (class "Default")
      (node (ref "CN5000") (pin "13") (pinfunction "13_13") (pintype "passive"))
      (node (ref "R5015") (pin "1") (pinfunction "1_1") (pintype "passive"))
      (node (ref "U5001") (pin "92") (pinfunction "PB6_92") (pintype "bidirectional"))
    )
    (net (code "89") (name "/MCU93") (class "Default")
      (node (ref "CN5000") (pin "14") (pinfunction "14_14") (pintype "passive"))
      (node (ref "R5017") (pin "1") (pinfunction "1_1") (pintype "passive"))
      (node (ref "U5001") (pin "93") (pinfunction "PB7_93") (pintype "bidirectional"))
    )
    (net (code "90") (name "/MCU94") (class "Default")
      (node (ref "CN5000") (pin "15") (pinfunction "15_15") (pintype "passive"))
      (node (ref "R5009") (pin "2") (pinfunction "2_2") (pintype "passive"))
      (node (ref "U5001") (pin "94") (pinfunction "BOOT0_94") (pintype "input"))
    )
    (net (code "91") (name "/MCU95") (class "Default")
      (node (ref "CN5000") (pin "16") (pinfunction "16_16") (pintype "passive"))
      (node (ref "U5001") (pin "95") (pinfunction "PB8_95") (pintype "bidirectional"))
    )
    (net (code "92") (name "/MCU96") (class "Default")
      (node (ref "CN5000") (pin "17") (pinfunction "17_17") (pintype "passive"))
      (node (ref "U5001") (pin "96") (pinfunction "PB9_96") (pintype "bidirectional"))
    )
    (net (code "93") (name "/MCU97") (class "Default")
      (node (ref "CN5000") (pin "18") (pinfunction "18_18") (pintype "passive"))
      (node (ref "R5032") (pin "1") (pinfunction "1_1") (pintype "passive"))
      (node (ref "U5001") (pin "97") (pinfunction "PE0_97") (pintype "bidirectional"))
      (node (ref "U5004") (pin "7") (pinfunction "WP_7") (pintype "passive"))
    )
    (net (code "94") (name "/MCU98") (class "Default")
      (node (ref "CN5000") (pin "19") (pinfunction "19_19") (pintype "passive"))
      (node (ref "U5001") (pin "98") (pinfunction "PE1_98") (pintype "bidirectional"))
    )
    (net (code "96") (name "/OSC32_IN") (class "Default")
      (node (ref "C5011") (pin "1") (pinfunction "1_1") (pintype "passive"))
      (node (ref "U5001") (pin "8") (pinfunction "PC14-OSC32_IN_8") (pintype "bidirectional"))
      (node (ref "X5001") (pin "1") (pinfunction "1_1") (pintype "passive"))
    )
    (net (code "97") (name "/OSC32_OUT") (class "Default")
      (node (ref "C5012") (pin "1") (pinfunction "1_1") (pintype "passive"))
      (node (ref "U5001") (pin "9") (pinfunction "PC15-OSC32_OUT_9") (pintype "bidirectional"))
      (node (ref "X5001") (pin "4") (pinfunction "4_4") (pintype "passive"))
    )
    (net (code "98") (name "/OSC_IN") (class "Default")
      (node (ref "C5007") (pin "1") (pinfunction "1_1") (pintype "passive"))
      (node (ref "U5001") (pin "12") (pinfunction "PH0-OSC_IN_12") (pintype "bidirectional"))
      (node (ref "X5000") (pin "1") (pinfunction "1_1") (pintype "passive"))
    )
    (net (code "99") (name "/OSC_OUT") (class "Default")
      (node (ref "C5008") (pin "1") (pinfunction "1_1") (pintype "passive"))
      (node (ref "U5001") (pin "13") (pinfunction "PH1-OSC_OUT_13") (pintype "bidirectional"))
      (node (ref "X5000") (pin "2") (pinfunction "2_2") (pintype "passive"))
    )
    (net (code "100") (name "/RESET#") (class "Default")
      (node (ref "B5001") (pin "1") (pinfunction "1_1") (pintype "passive"))
      (node (ref "C5013") (pin "1") (pinfunction "1_1") (pintype "passive"))
      (node (ref "R5016") (pin "1") (pinfunction "1_1") (pintype "passive"))
    )
    (net (code "101") (name "/RS485_RX") (class "Default")
      (node (ref "SB5004") (pin "2") (pinfunction "2_2") (pintype "passive"))
      (node (ref "SB5006") (pin "2") (pinfunction "2_2") (pintype "passive"))
    )
    (net (code "102") (name "/RS485_TX") (class "Default")
      (node (ref "SB5005") (pin "2") (pinfunction "2_2") (pintype "passive"))
      (node (ref "SB5007") (pin "2") (pinfunction "2_2") (pintype "passive"))
    )
    (net (code "103") (name "/SD_CS_LLS") (class "Default")
      (node (ref "U5002") (pin "8") (pinfunction "3Y_8") (pintype "passive"))
      (node (ref "U5003") (pin "2") (pinfunction "2_2") (pintype "passive"))
    )
    (net (code "104") (name "/SD_DI_LLS") (class "Default")
      (node (ref "U5002") (pin "3") (pinfunction "1Y_3") (pintype "passive"))
      (node (ref "U5003") (pin "3") (pinfunction "3_3") (pintype "passive"))
    )
    (net (code "105") (name "/SD_SCK_LLS") (class "Default")
      (node (ref "U5002") (pin "6") (pinfunction "2Y_6") (pintype "passive"))
      (node (ref "U5003") (pin "5") (pinfunction "5_5") (pintype "passive"))
    )
    (net (code "106") (name "/USB1_N") (class "Default")
      (node (ref "CN5001") (pin "17") (pinfunction "17_17") (pintype "passive"))
      (node (ref "R5001") (pin "2") (pinfunction "2_2") (pintype "passive"))
      (node (ref "U5001") (pin "70") (pinfunction "PA11_70") (pintype "bidirectional"))
    )
    (net (code "107") (name "/USB1_P") (class "Default")
      (node (ref "CN5001") (pin "19") (pinfunction "19_19") (pintype "passive"))
      (node (ref "R5010") (pin "2") (pinfunction "2_2") (pintype "passive"))
      (node (ref "U5001") (pin "71") (pinfunction "PA12_71") (pintype "bidirectional"))
    )
    (net (code "108") (name "GND") (class "Default")
      (node (ref "B5001") (pin "2") (pinfunction "2_2") (pintype "passive"))
      (node (ref "B5002") (pin "2") (pinfunction "2_2") (pintype "passive"))
      (node (ref "C5000") (pin "2") (pinfunction "2_2") (pintype "passive"))
      (node (ref "C5001") (pin "2") (pinfunction "2_2") (pintype "passive"))
      (node (ref "C5002") (pin "2") (pinfunction "2_2") (pintype "passive"))
      (node (ref "C5003") (pin "2") (pinfunction "2_2") (pintype "passive"))
      (node (ref "C5004") (pin "2") (pinfunction "2_2") (pintype "passive"))
      (node (ref "C5005") (pin "2") (pinfunction "2_2") (pintype "passive"))
      (node (ref "C5006") (pin "2") (pinfunction "2_2") (pintype "passive"))
      (node (ref "C5007") (pin "2") (pinfunction "2_2") (pintype "passive"))
      (node (ref "C5008") (pin "2") (pinfunction "2_2") (pintype "passive"))
      (node (ref "C5009") (pin "2") (pinfunction "2_2") (pintype "passive"))
      (node (ref "C5010") (pin "2") (pinfunction "2_2") (pintype "passive"))
      (node (ref "C5011") (pin "2") (pinfunction "2_2") (pintype "passive"))
      (node (ref "C5012") (pin "2") (pinfunction "2_2") (pintype "passive"))
      (node (ref "C5013") (pin "2") (pinfunction "2_2") (pintype "passive"))
      (node (ref "C5014") (pin "2") (pinfunction "2_2") (pintype "passive"))
      (node (ref "C5015") (pin "2") (pinfunction "2_2") (pintype "passive"))
      (node (ref "C5016") (pin "2") (pinfunction "2_2") (pintype "passive"))
      (node (ref "C5017") (pin "2") (pinfunction "2_2") (pintype "passive"))
      (node (ref "C5018") (pin "2") (pinfunction "2_2") (pintype "passive"))
      (node (ref "CN5003") (pin "8") (pinfunction "8_8") (pintype "passive"))
      (node (ref "D5000") (pin "2") (pinfunction "2_2") (pintype "passive"))
      (node (ref "D5000") (pin "4") (pinfunction "4_4") (pintype "passive"))
      (node (ref "D5000") (pin "6") (pinfunction "6_6") (pintype "passive"))
      (node (ref "H5000") (pin "10") (pinfunction "10_10") (pintype "passive"))
      (node (ref "H5000") (pin "6") (pinfunction "6_6") (pintype "passive"))
      (node (ref "H5000") (pin "8") (pinfunction "8_8") (pintype "passive"))
      (node (ref "J5000") (pin "1") (pinfunction "1_1") (pintype "passive"))
      (node (ref "R5032") (pin "2") (pinfunction "2_2") (pintype "passive"))
      (node (ref "U5000") (pin "1") (pinfunction "C_1") (pintype "passive"))
      (node (ref "U5001") (pin "10") (pinfunction "VSS_10") (pintype "power_in"))
      (node (ref "U5001") (pin "19") (pinfunction "VSSA_19") (pintype "power_in"))
      (node (ref "U5001") (pin "26") (pinfunction "VSS_26") (pintype "power_in"))
      (node (ref "U5001") (pin "49") (pinfunction "VSS_49") (pintype "power_in"))
      (node (ref "U5001") (pin "74") (pinfunction "VSS_74") (pintype "power_in"))
      (node (ref "U5001") (pin "99") (pinfunction "VSS_99") (pintype "power_in"))
      (node (ref "U5002") (pin "1") (pinfunction "1~{OE}_1") (pintype "passive"))
      (node (ref "U5002") (pin "10") (pinfunction "3~{OE}_10") (pintype "passive"))
      (node (ref "U5002") (pin "13") (pinfunction "4~{OE}_13") (pintype "passive"))
      (node (ref "U5002") (pin "4") (pinfunction "2~{OE}_4") (pintype "passive"))
      (node (ref "U5002") (pin "7") (pinfunction "GND_7") (pintype "passive"))
      (node (ref "U5003") (pin "6") (pinfunction "6_6") (pintype "passive"))
      (node (ref "U5003") (pin "G") (pinfunction "G_G") (pintype "passive"))
      (node (ref "U5004") (pin "1") (pinfunction "A0_1") (pintype "passive"))
      (node (ref "U5004") (pin "2") (pinfunction "A1_2") (pintype "passive"))
      (node (ref "U5004") (pin "3") (pinfunction "A2_3") (pintype "passive"))
      (node (ref "U5004") (pin "4") (pinfunction "GND_4") (pintype "power_in"))
      (node (ref "U5005") (pin "4") (pinfunction "GND_4") (pintype "passive"))
      (node (ref "U5005") (pin "5") (pinfunction "A2_5") (pintype "passive"))
      (node (ref "U5005") (pin "6") (pinfunction "A1_6") (pintype "passive"))
      (node (ref "X5001") (pin "2") (pinfunction "2_2") (pintype "passive"))
      (node (ref "X5001") (pin "3") (pinfunction "3_3") (pintype "passive"))
    )
    (net (code "109") (name "Net-(B5002-Pad1)") (class "Default")
      (node (ref "B5002") (pin "1") (pinfunction "1_1") (pintype "passive"))
      (node (ref "C5014") (pin "1") (pinfunction "1_1") (pintype "passive"))
      (node (ref "R5008") (pin "2") (pinfunction "2_2") (pintype "passive"))
    )
    (net (code "110") (name "Net-(C5009-Pad1)") (class "Default")
      (node (ref "C5009") (pin "1") (pinfunction "1_1") (pintype "passive"))
      (node (ref "U5001") (pin "73") (pinfunction "VCAP_73") (pintype "passive"))
    )
    (net (code "111") (name "Net-(C5010-Pad1)") (class "Default")
      (node (ref "C5010") (pin "1") (pinfunction "1_1") (pintype "passive"))
      (node (ref "U5001") (pin "48") (pinfunction "VCAP_48") (pintype "passive"))
    )
    (net (code "112") (name "Net-(D5001-Pad1)") (class "Default")
      (node (ref "D5001") (pin "1") (pinfunction "1_1") (pintype "passive"))
      (node (ref "R5011") (pin "2") (pinfunction "2_2") (pintype "passive"))
    )
    (net (code "113") (name "Net-(J5000-Pad2)") (class "Default")
      (node (ref "J5000") (pin "2") (pinfunction "2_2") (pintype "passive"))
      (node (ref "R5009") (pin "1") (pinfunction "1_1") (pintype "passive"))
    )
    (net (code "114") (name "Net-(S5001-Pad3)") (class "Default")
      (node (ref "S5001") (pin "3") (pinfunction "3_3") (pintype "passive"))
      (node (ref "SB5009") (pin "2") (pinfunction "2_2") (pintype "passive"))
      (node (ref "SB5010") (pin "2") (pinfunction "2_2") (pintype "passive"))
    )
    (net (code "115") (name "Net-(S5001-Pad4)") (class "Default")
      (node (ref "S5001") (pin "4") (pinfunction "4_4") (pintype "passive"))
      (node (ref "SB5008") (pin "2") (pinfunction "2_2") (pintype "passive"))
      (node (ref "SB5011") (pin "2") (pinfunction "2_2") (pintype "passive"))
    )
    (net (code "116") (name "Net-(U5001C-VDDA)") (class "Default")
      (node (ref "B5000") (pin "2") (pinfunction "2_2") (pintype "passive"))
      (node (ref "R5000") (pin "1") (pinfunction "1_1") (pintype "passive"))
      (node (ref "U5001") (pin "21") (pinfunction "VDDA_21") (pintype "power_in"))
    )
    (net (code "117") (name "Net-(U5001C-VREF+)") (class "Default")
      (node (ref "R5000") (pin "2") (pinfunction "2_2") (pintype "passive"))
      (node (ref "U5001") (pin "20") (pinfunction "VREF+_20") (pintype "power_in"))
    )
    (net (code "118") (name "Net-(U5002-1A)") (class "Default")
      (node (ref "R5026") (pin "2") (pinfunction "2_2") (pintype "passive"))
      (node (ref "U5002") (pin "2") (pinfunction "1A_2") (pintype "passive"))
    )
    (net (code "119") (name "Net-(U5002-2A)") (class "Default")
      (node (ref "R5027") (pin "2") (pinfunction "2_2") (pintype "passive"))
      (node (ref "U5002") (pin "5") (pinfunction "2A_5") (pintype "passive"))
    )
    (net (code "120") (name "Net-(U5002-3A)") (class "Default")
      (node (ref "R5028") (pin "2") (pinfunction "2_2") (pintype "passive"))
      (node (ref "U5002") (pin "9") (pinfunction "3A_9") (pintype "passive"))
    )
    (net (code "121") (name "Net-(U5002-4A)") (class "Default")
      (node (ref "R5029") (pin "2") (pinfunction "2_2") (pintype "passive"))
      (node (ref "U5002") (pin "12") (pinfunction "4A_12") (pintype "passive"))
    )
    (net (code "122") (name "Net-(U5005-A0)") (class "Default")
      (node (ref "R5004") (pin "1") (pinfunction "1_1") (pintype "passive"))
      (node (ref "U5005") (pin "7") (pinfunction "A0_7") (pintype "passive"))
    )
    (net (code "123") (name "Net-(U5005-OS)") (class "Default")
      (node (ref "D5001") (pin "2") (pinfunction "2_2") (pintype "passive"))
      (node (ref "U5005") (pin "3") (pinfunction "OS_3") (pintype "passive"))
    )
    (net (code "124") (name "VCC_+5_REF_A") (class "Default")
      (node (ref "C5016") (pin "1") (pinfunction "1_1") (pintype "passive"))
      (node (ref "C5018") (pin "1") (pinfunction "1_1") (pintype "passive"))
      (node (ref "R5002") (pin "2") (pinfunction "2_2") (pintype "passive"))
      (node (ref "R5003") (pin "2") (pinfunction "2_2") (pintype "passive"))
      (node (ref "R5004") (pin "2") (pinfunction "2_2") (pintype "passive"))
      (node (ref "R5011") (pin "1") (pinfunction "1_1") (pintype "passive"))
      (node (ref "R5030") (pin "1") (pinfunction "1_1") (pintype "passive"))
      (node (ref "R5031") (pin "1") (pinfunction "1_1") (pintype "passive"))
      (node (ref "U5004") (pin "8") (pinfunction "VCC_8") (pintype "power_in"))
      (node (ref "U5005") (pin "8") (pinfunction "VCC_8") (pintype "passive"))
    )
    (net (code "125") (name "VCC_3V3_REF_A") (class "Default")
      (node (ref "B5000") (pin "1") (pinfunction "1_1") (pintype "passive"))
      (node (ref "C5000") (pin "1") (pinfunction "1_1") (pintype "passive"))
      (node (ref "C5001") (pin "1") (pinfunction "1_1") (pintype "passive"))
      (node (ref "C5002") (pin "1") (pinfunction "1_1") (pintype "passive"))
      (node (ref "C5003") (pin "1") (pinfunction "1_1") (pintype "passive"))
      (node (ref "C5004") (pin "1") (pinfunction "1_1") (pintype "passive"))
      (node (ref "C5005") (pin "1") (pinfunction "1_1") (pintype "passive"))
      (node (ref "C5006") (pin "1") (pinfunction "1_1") (pintype "passive"))
      (node (ref "C5015") (pin "1") (pinfunction "1_1") (pintype "passive"))
      (node (ref "C5017") (pin "1") (pinfunction "1_1") (pintype "passive"))
      (node (ref "J5000") (pin "3") (pinfunction "3_3") (pintype "passive"))
      (node (ref "U5001") (pin "100") (pinfunction "VDD_100") (pintype "power_in"))
      (node (ref "U5001") (pin "11") (pinfunction "VDD_11") (pintype "power_in"))
      (node (ref "U5001") (pin "27") (pinfunction "VDD_27") (pintype "power_in"))
      (node (ref "U5001") (pin "50") (pinfunction "VDD_50") (pintype "power_in"))
      (node (ref "U5001") (pin "75") (pinfunction "VDD_75") (pintype "power_in"))
      (node (ref "U5002") (pin "14") (pinfunction "VCC_14") (pintype "passive"))
      (node (ref "U5003") (pin "4") (pinfunction "4_4") (pintype "passive"))
    )
    (net (code "126") (name "unconnected-(CN5000-Pad20)") (class "Default")
      (node (ref "CN5000") (pin "20") (pinfunction "20_20") (pintype "passive+no_connect"))
    )
    (net (code "127") (name "unconnected-(CN5002-Pad2)") (class "Default")
      (node (ref "CN5002") (pin "2") (pinfunction "2_2") (pintype "passive+no_connect"))
    )
    (net (code "128") (name "unconnected-(CN5002-Pad19)") (class "Default")
      (node (ref "CN5002") (pin "19") (pinfunction "19_19") (pintype "passive+no_connect"))
    )
    (net (code "129") (name "unconnected-(CN5002-Pad20)") (class "Default")
      (node (ref "CN5002") (pin "20") (pinfunction "20_20") (pintype "passive+no_connect"))
    )
    (net (code "130") (name "unconnected-(U5003-Pad1)") (class "Default")
      (node (ref "U5003") (pin "1") (pinfunction "1_1") (pintype "passive+no_connect"))
    )
    (net (code "131") (name "unconnected-(U5003-Pad8)") (class "Default")
      (node (ref "U5003") (pin "8") (pinfunction "8_8") (pintype "passive+no_connect"))
    )
    (net (code "132") (name "unconnected-(U5003-PadCD)") (class "Default")
      (node (ref "U5003") (pin "CD") (pinfunction "CD_CD") (pintype "passive+no_connect"))
    )
  )
)
